# DAC_filter_stage.net
KiCad netlist of a schematic drawn in Altium Designer
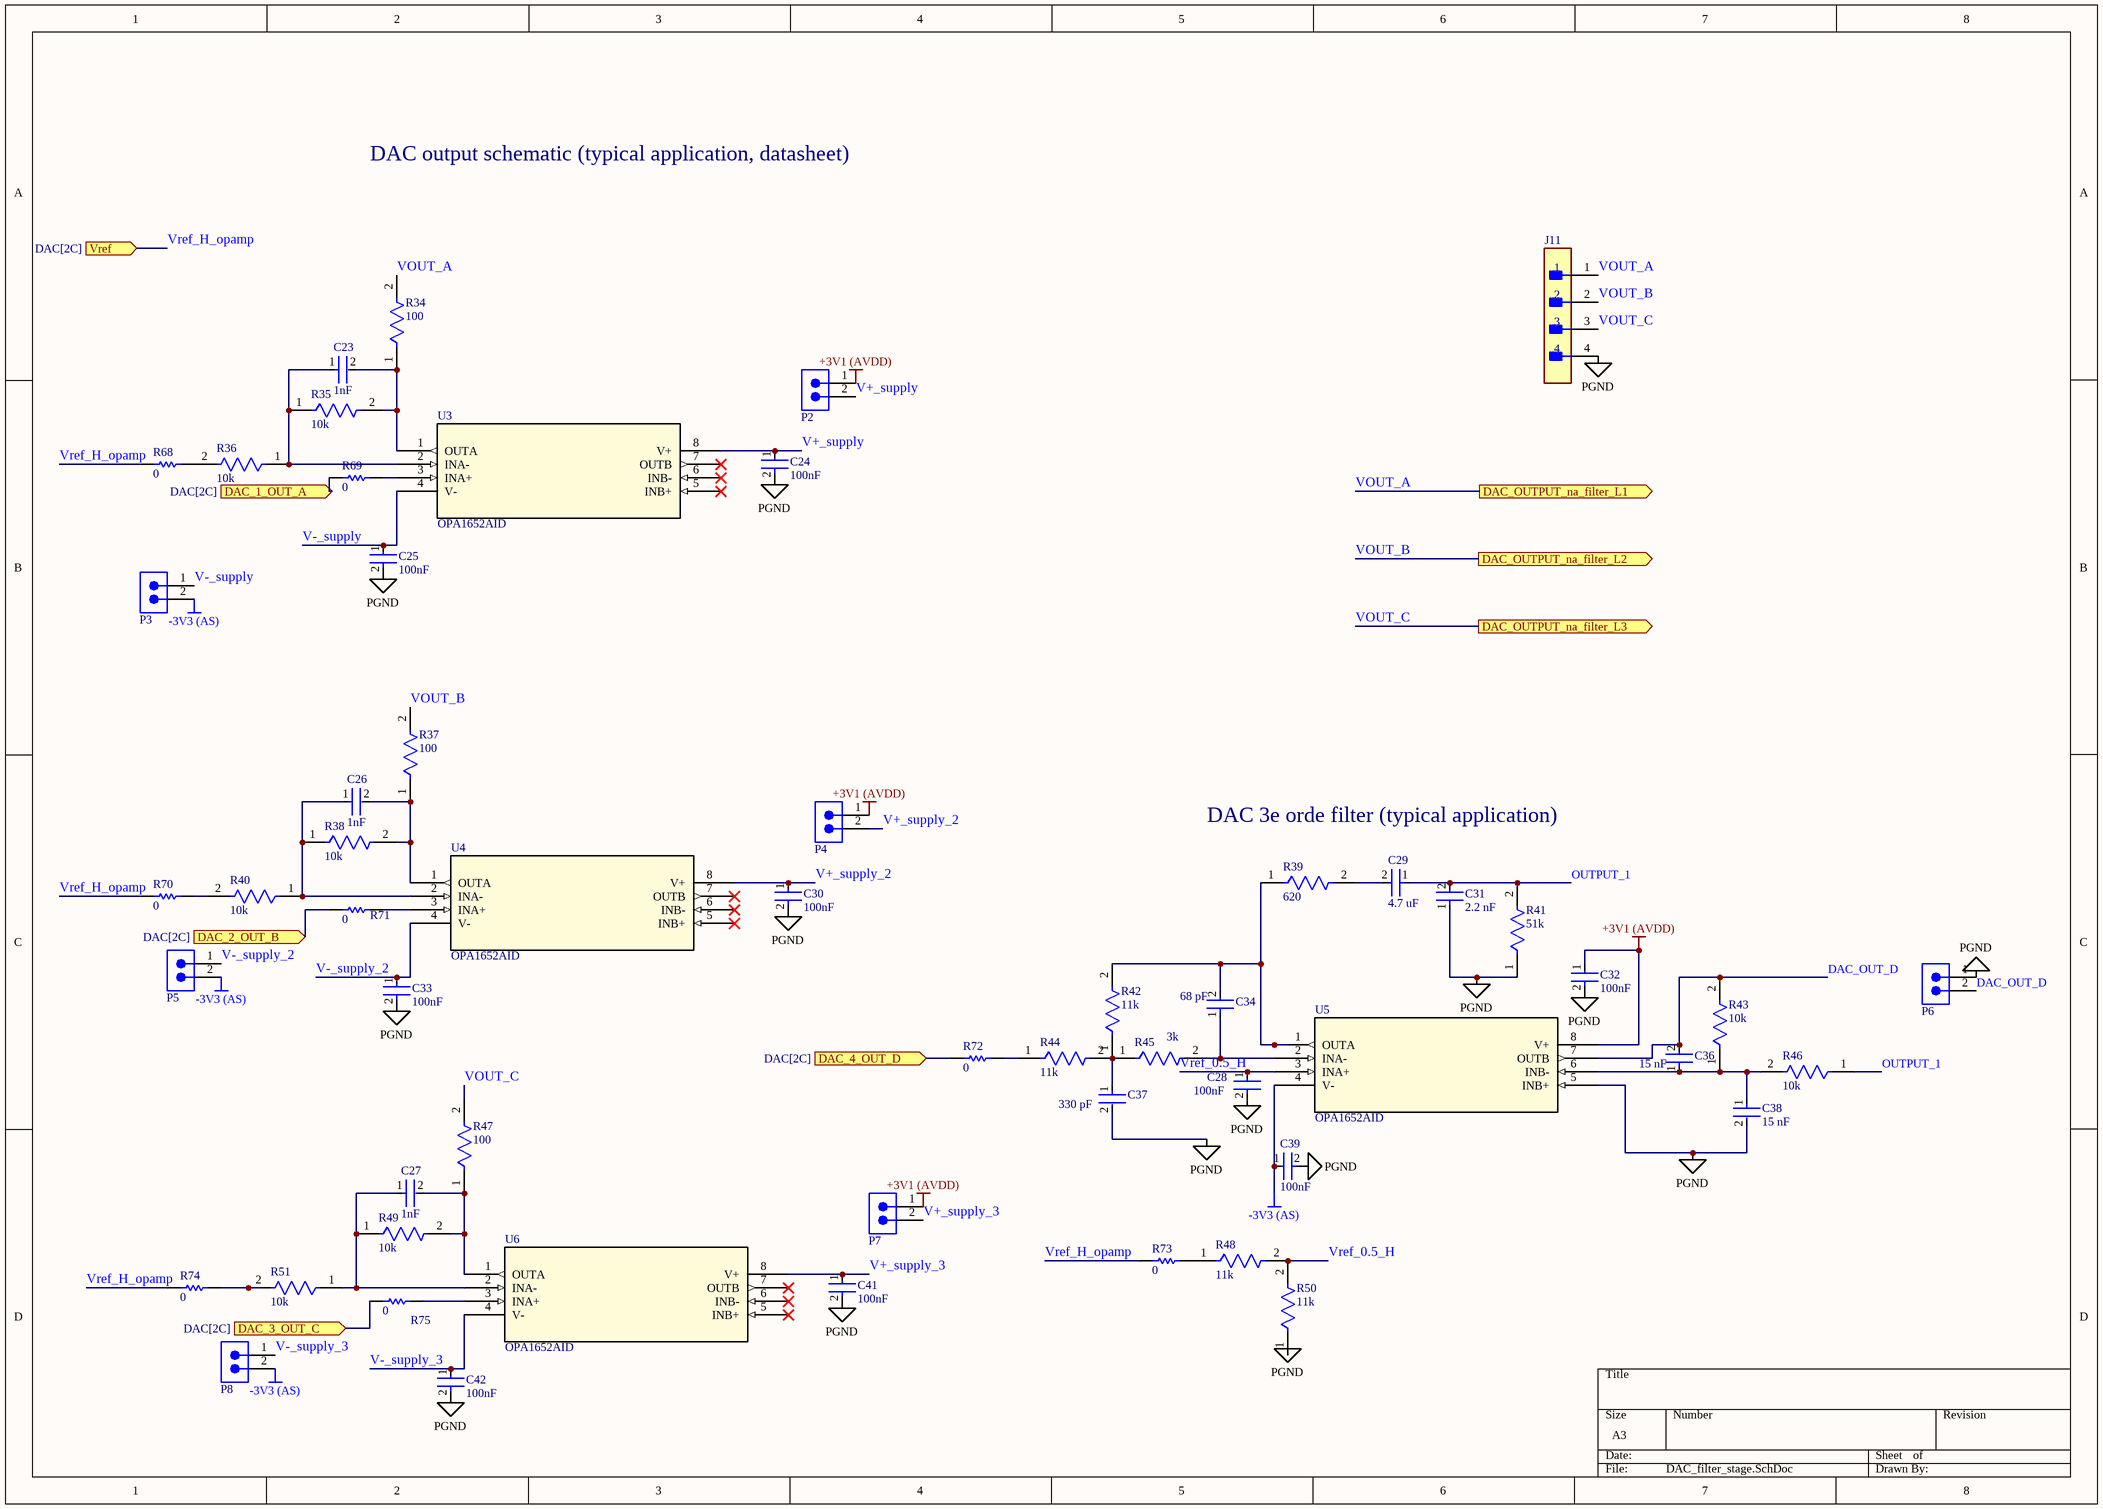
[diagram p0: DAC_filter_stage.SchDoc]

(export (version "E")
  (design (tool "Eeschema 10.0.6"))
  (components
    (comp (ref "C23")
      (value "1nF")
      (footprint "FP-CC0603-DA-MFG")
      (description "General Purpose Ceramic Capacitor, 0603, 1nF, 10%, X7R, 15%, 50V")
      (fields
        (field (name "OCTOPART") "https://octopart.com/cc0603krx7r7bb104-yageo-192941")
        (field (name "TOLERANCE") "0.1")
      )
      (libsource (lib "Altium Content Vault") (part "11868f565c42a9108669ba33697ecf6"))
    )
    (comp (ref "C24")
      (value "100nF")
      (footprint "FP-GRM15-MFG")
      (description "CAP CER 0.1UF 16V X7R 0402")
      (fields (field (name "MANUFACTURER PART NUMBER") "GRM155R71C104KA88D") (field (name "TOLERANCE") "10%"))
      (libsource (lib "Altium Content Vault") (part "236180d848d6139a670b325ea6854c9"))
    )
    (comp (ref "C25")
      (value "100nF")
      (footprint "FP-GRM15-MFG")
      (description "CAP CER 0.1UF 16V X7R 0402")
      (fields (field (name "MANUFACTURER PART NUMBER") "GRM155R71C104KA88D") (field (name "TOLERANCE") "10%"))
      (libsource (lib "Altium Content Vault") (part "236180d848d6139a670b325ea6854c9"))
    )
    (comp (ref "C26")
      (value "1nF")
      (footprint "FP-CC0603-DA-MFG")
      (description "General Purpose Ceramic Capacitor, 0603, 1nF, 10%, X7R, 15%, 50V")
      (fields
        (field (name "OCTOPART") "https://octopart.com/cc0603krx7r7bb104-yageo-192941")
        (field (name "TOLERANCE") "0.1")
      )
      (libsource (lib "Altium Content Vault") (part "11868f565c42a9108669ba33697ecf6"))
    )
    (comp (ref "C27")
      (value "1nF")
      (footprint "FP-CC0603-DA-MFG")
      (description "General Purpose Ceramic Capacitor, 0603, 1nF, 10%, X7R, 15%, 50V")
      (fields
        (field (name "OCTOPART") "https://octopart.com/cc0603krx7r7bb104-yageo-192941")
        (field (name "TOLERANCE") "0.1")
      )
      (libsource (lib "Altium Content Vault") (part "11868f565c42a9108669ba33697ecf6"))
    )
    (comp (ref "C28")
      (value "100nF")
      (footprint "FP-GRM15-MFG")
      (description "CAP CER 0.1UF 16V X7R 0402")
      (fields (field (name "MANUFACTURER PART NUMBER") "GRM155R71C104KA88D") (field (name "TOLERANCE") "10%"))
      (libsource (lib "Altium Content Vault") (part "236180d848d6139a670b325ea6854c9"))
    )
    (comp (ref "C29")
      (value "4.7 uF")
      (footprint "FP-C0603C-CF-MFG")
      (description "CAP CER 4.7 UF 50V 5% X7R 0603")
      (fields (field (name "TOLERANCE") "0.05") (field (name "MANUFACTURER PART NUMBER") "C0603C104J5RACTU"))
      (libsource (lib "Altium Content Vault") (part "b4654b650e69147ec39a6b967a45e02"))
    )
    (comp (ref "C30")
      (value "100nF")
      (footprint "FP-GRM15-MFG")
      (description "CAP CER 0.1UF 16V X7R 0402")
      (fields (field (name "MANUFACTURER PART NUMBER") "GRM155R71C104KA88D") (field (name "TOLERANCE") "10%"))
      (libsource (lib "Altium Content Vault") (part "236180d848d6139a670b325ea6854c9"))
    )
    (comp (ref "C31")
      (value "2.2 nF")
      (footprint "FP-AC0603-MFG")
      (description "AC0603 2.2 pF NP0 5.00% 50 V")
      (fields
        (field (name "TOLERANCE") "0.05")
        (field (name "OCTOPART") "https://octopart.com/ac0603jrnpo9bn271-yageo-87214073")
      )
      (libsource (lib "Altium Content Vault") (part "11868f565c42a9108669ba33697ecf6"))
    )
    (comp (ref "C32")
      (value "100nF")
      (footprint "FP-GRM15-MFG")
      (description "CAP CER 0.1UF 16V X7R 0402")
      (fields (field (name "MANUFACTURER PART NUMBER") "GRM155R71C104KA88D") (field (name "TOLERANCE") "10%"))
      (libsource (lib "Altium Content Vault") (part "236180d848d6139a670b325ea6854c9"))
    )
    (comp (ref "C33")
      (value "100nF")
      (footprint "FP-GRM15-MFG")
      (description "CAP CER 0.1UF 16V X7R 0402")
      (fields (field (name "MANUFACTURER PART NUMBER") "GRM155R71C104KA88D") (field (name "TOLERANCE") "10%"))
      (libsource (lib "Altium Content Vault") (part "236180d848d6139a670b325ea6854c9"))
    )
    (comp (ref "C34")
      (value "68 pF")
      (footprint "FP-AC0603-MFG")
      (description "AC0603 68 pF NP0 5.00% 50 V")
      (fields
        (field (name "TOLERANCE") "0.05")
        (field (name "OCTOPART") "https://octopart.com/ac0603jrnpo9bn271-yageo-87214073")
      )
      (libsource (lib "Altium Content Vault") (part "11868f565c42a9108669ba33697ecf6"))
    )
    (comp (ref "C36")
      (value "15 nF")
      (footprint "FP-C0603C-CF-MFG")
      (fields
        (field (name "TOLERANCE") "0.05")
        (field (name "MANUFACTURER PART NUMBER") "C0603C104J5RACTU")
        (field (name "OCTOPART") "https://octopart.com/c0603c104j5ractu-kemet-10440638")
      )
      (libsource (lib "Altium Content Vault") (part "b4654b650e69147ec39a6b967a45e02"))
    )
    (comp (ref "C37")
      (value "330 pF")
      (footprint "FP-AC0603-MFG")
      (description "AC0603 330 pF NP0 5.00% 50 V")
      (fields
        (field (name "TOLERANCE") "0.05")
        (field (name "OCTOPART") "https://octopart.com/ac0603jrnpo9bn271-yageo-87214073")
      )
      (libsource (lib "Altium Content Vault") (part "11868f565c42a9108669ba33697ecf6"))
    )
    (comp (ref "C38")
      (value "15 nF")
      (footprint "FP-C0603C-CF-MFG")
      (fields
        (field (name "TOLERANCE") "0.05")
        (field (name "MANUFACTURER PART NUMBER") "C0603C104J5RACTU")
        (field (name "OCTOPART") "https://octopart.com/c0603c104j5ractu-kemet-10440638")
      )
      (libsource (lib "Altium Content Vault") (part "b4654b650e69147ec39a6b967a45e02"))
    )
    (comp (ref "C39")
      (value "100nF")
      (footprint "FP-GRM15-MFG")
      (description "CAP CER 0.1UF 16V X7R 0402")
      (fields (field (name "MANUFACTURER PART NUMBER") "GRM155R71C104KA88D") (field (name "TOLERANCE") "10%"))
      (libsource (lib "Altium Content Vault") (part "236180d848d6139a670b325ea6854c9"))
    )
    (comp (ref "C41")
      (value "100nF")
      (footprint "FP-GRM15-MFG")
      (description "CAP CER 0.1UF 16V X7R 0402")
      (fields (field (name "MANUFACTURER PART NUMBER") "GRM155R71C104KA88D") (field (name "TOLERANCE") "10%"))
      (libsource (lib "Altium Content Vault") (part "236180d848d6139a670b325ea6854c9"))
    )
    (comp (ref "C42")
      (value "100nF")
      (footprint "FP-GRM15-MFG")
      (description "CAP CER 0.1UF 16V X7R 0402")
      (fields (field (name "MANUFACTURER PART NUMBER") "GRM155R71C104KA88D") (field (name "TOLERANCE") "10%"))
      (libsource (lib "Altium Content Vault") (part "236180d848d6139a670b325ea6854c9"))
    )
    (comp (ref "J11")
      (value "TSW-104-22-G-S")
      (footprint "FP-TSW-104-22-G-S-MFG")
      (description "GENERIC PART NUMBER: GPHA-1X04\r\nCONN HEADER VERT 4POS 2.54MM")
      (fields (field (name "GENERIC PART NUMBER") "GPHA-1X04"))
      (libsource (lib "Altium Content Vault") (part "299a8cea1bdcbc3624fe62c390fa72c"))
    )
    (comp (ref "P2")
      (value "TSW-102-26-T-S")
      (footprint "SMTC-TSW-102-26-XX-S")
      (description "0.025\" SQ Post Header, Through-hole, Vertical, -55 to 105 degC, 2.54 mm Pitch, 2-Pin, Male, RoHS")
      (fields (field (name "MANUFACTURER") "Samtec"))
      (libsource (lib "Altium Content Vault") (part "SMTC-TSW-102-X-X-S-X"))
    )
    (comp (ref "P3")
      (value "TSW-102-26-T-S")
      (footprint "SMTC-TSW-102-26-XX-S")
      (description "0.025\" SQ Post Header, Through-hole, Vertical, -55 to 105 degC, 2.54 mm Pitch, 2-Pin, Male, RoHS")
      (fields (field (name "MANUFACTURER") "Samtec"))
      (libsource (lib "Altium Content Vault") (part "SMTC-TSW-102-X-X-S-X"))
    )
    (comp (ref "P4")
      (value "TSW-102-26-T-S")
      (footprint "SMTC-TSW-102-26-XX-S")
      (description "0.025\" SQ Post Header, Through-hole, Vertical, -55 to 105 degC, 2.54 mm Pitch, 2-Pin, Male, RoHS")
      (fields (field (name "MANUFACTURER") "Samtec"))
      (libsource (lib "Altium Content Vault") (part "SMTC-TSW-102-X-X-S-X"))
    )
    (comp (ref "P5")
      (value "TSW-102-26-T-S")
      (footprint "SMTC-TSW-102-26-XX-S")
      (description "0.025\" SQ Post Header, Through-hole, Vertical, -55 to 105 degC, 2.54 mm Pitch, 2-Pin, Male, RoHS")
      (fields (field (name "MANUFACTURER") "Samtec"))
      (libsource (lib "Altium Content Vault") (part "SMTC-TSW-102-X-X-S-X"))
    )
    (comp (ref "P6")
      (value "TSW-102-26-T-S")
      (footprint "SMTC-TSW-102-26-XX-S")
      (description "0.025\" SQ Post Header, Through-hole, Vertical, -55 to 105 degC, 2.54 mm Pitch, 2-Pin, Male, RoHS")
      (fields (field (name "MANUFACTURER") "Samtec"))
      (libsource (lib "Altium Content Vault") (part "SMTC-TSW-102-X-X-S-X"))
    )
    (comp (ref "P7")
      (value "TSW-102-26-T-S")
      (footprint "SMTC-TSW-102-26-XX-S")
      (description "0.025\" SQ Post Header, Through-hole, Vertical, -55 to 105 degC, 2.54 mm Pitch, 2-Pin, Male, RoHS")
      (fields (field (name "MANUFACTURER") "Samtec"))
      (libsource (lib "Altium Content Vault") (part "SMTC-TSW-102-X-X-S-X"))
    )
    (comp (ref "P8")
      (value "TSW-102-26-T-S")
      (footprint "SMTC-TSW-102-26-XX-S")
      (description "0.025\" SQ Post Header, Through-hole, Vertical, -55 to 105 degC, 2.54 mm Pitch, 2-Pin, Male, RoHS")
      (fields (field (name "MANUFACTURER") "Samtec"))
      (libsource (lib "Altium Content Vault") (part "SMTC-TSW-102-X-X-S-X"))
    )
    (comp (ref "R34")
      (value "100")
      (footprint "FP-RC1608-IPC_B")
      (description "Res Thick Film 0603 100Ω 1% 0.1W ±100ppm/°C Molded SMD T/R")
      (fields (field (name "TOLERANCE") "1%"))
      (libsource (lib "Altium Content Vault") (part "1029c3af85768c4190bb7ad29bc67b5"))
    )
    (comp (ref "R35")
      (value "10k")
      (footprint "FP-RC1608-IPC_B")
      (description "Res Thick Film 0603 11kΩ 1% 0.1W ±100ppm/°C Molded SMD T/R")
      (fields (field (name "TOLERANCE") "1%"))
      (libsource (lib "Altium Content Vault") (part "1029c3af85768c4190bb7ad29bc67b5"))
    )
    (comp (ref "R36")
      (value "10k")
      (footprint "FP-RC1608-IPC_B")
      (description "Res Thick Film 0603 11kΩ 1% 0.1W ±100ppm/°C Molded SMD T/R")
      (fields (field (name "TOLERANCE") "1%"))
      (libsource (lib "Altium Content Vault") (part "1029c3af85768c4190bb7ad29bc67b5"))
    )
    (comp (ref "R37")
      (value "100")
      (footprint "FP-RC1608-IPC_B")
      (description "Res Thick Film 0603 100Ω 1% 0.1W ±100ppm/°C Molded SMD T/R")
      (fields (field (name "TOLERANCE") "1%"))
      (libsource (lib "Altium Content Vault") (part "1029c3af85768c4190bb7ad29bc67b5"))
    )
    (comp (ref "R38")
      (value "10k")
      (footprint "FP-RC1608-IPC_B")
      (description "Res Thick Film 0603 11kΩ 1% 0.1W ±100ppm/°C Molded SMD T/R")
      (fields (field (name "TOLERANCE") "1%"))
      (libsource (lib "Altium Content Vault") (part "1029c3af85768c4190bb7ad29bc67b5"))
    )
    (comp (ref "R39")
      (value "620")
      (footprint "FP-RC1608-IPC_B")
      (description "Res Thick Film 0603 620Ω 1% 0.1W ±100ppm/°C Molded SMD T/R")
      (fields (field (name "TOLERANCE") "1%"))
      (libsource (lib "Altium Content Vault") (part "1029c3af85768c4190bb7ad29bc67b5"))
    )
    (comp (ref "R40")
      (value "10k")
      (footprint "FP-RC1608-IPC_B")
      (description "Res Thick Film 0603 11kΩ 1% 0.1W ±100ppm/°C Molded SMD T/R")
      (fields (field (name "TOLERANCE") "1%"))
      (libsource (lib "Altium Content Vault") (part "1029c3af85768c4190bb7ad29bc67b5"))
    )
    (comp (ref "R41")
      (value "51k")
      (footprint "FP-RC1608-IPC_B")
      (description "Res Thick Film 0603 51kΩ 1% 0.1W ±100ppm/°C Molded SMD T/R")
      (fields (field (name "TOLERANCE") "1%"))
      (libsource (lib "Altium Content Vault") (part "1029c3af85768c4190bb7ad29bc67b5"))
    )
    (comp (ref "R42")
      (value "11k")
      (footprint "FP-RC1608-IPC_B")
      (description "Res Thick Film 0603 11kΩ 1% 0.1W ±100ppm/°C Molded SMD T/R")
      (fields (field (name "TOLERANCE") "1%"))
      (libsource (lib "Altium Content Vault") (part "1029c3af85768c4190bb7ad29bc67b5"))
    )
    (comp (ref "R43")
      (value "10k")
      (footprint "FP-RC1608-IPC_B")
      (fields (field (name "TOLERANCE") "1%"))
      (libsource (lib "Altium Content Vault") (part "1029c3af85768c4190bb7ad29bc67b5"))
    )
    (comp (ref "R44")
      (value "11k")
      (footprint "FP-RC1608-IPC_B")
      (description "Res Thick Film 0603 11kΩ 1% 0.1W ±100ppm/°C Molded SMD T/R")
      (fields (field (name "TOLERANCE") "1%"))
      (libsource (lib "Altium Content Vault") (part "1029c3af85768c4190bb7ad29bc67b5"))
    )
    (comp (ref "R45")
      (value "3k")
      (footprint "FP-RC1608-IPC_B")
      (description "Res Thick Film 0603 3kΩ 1% 0.1W ±100ppm/°C Molded SMD T/R")
      (fields (field (name "TOLERANCE") "1%"))
      (libsource (lib "Altium Content Vault") (part "1029c3af85768c4190bb7ad29bc67b5"))
    )
    (comp (ref "R46")
      (value "10k")
      (footprint "FP-RC1608-IPC_B")
      (fields (field (name "TOLERANCE") "1%"))
      (libsource (lib "Altium Content Vault") (part "1029c3af85768c4190bb7ad29bc67b5"))
    )
    (comp (ref "R47")
      (value "100")
      (footprint "FP-RC1608-IPC_B")
      (description "Res Thick Film 0603 100Ω 1% 0.1W ±100ppm/°C Molded SMD T/R")
      (fields (field (name "TOLERANCE") "1%"))
      (libsource (lib "Altium Content Vault") (part "1029c3af85768c4190bb7ad29bc67b5"))
    )
    (comp (ref "R48")
      (value "11k")
      (footprint "FP-RC1608-IPC_B")
      (description "Res Thick Film 0603 11kΩ 1% 0.1W ±100ppm/°C Molded SMD T/R")
      (fields (field (name "TOLERANCE") "1%"))
      (libsource (lib "Altium Content Vault") (part "1029c3af85768c4190bb7ad29bc67b5"))
    )
    (comp (ref "R49")
      (value "10k")
      (footprint "FP-RC1608-IPC_B")
      (description "Res Thick Film 0603 11kΩ 1% 0.1W ±100ppm/°C Molded SMD T/R")
      (fields (field (name "TOLERANCE") "1%"))
      (libsource (lib "Altium Content Vault") (part "1029c3af85768c4190bb7ad29bc67b5"))
    )
    (comp (ref "R50")
      (value "11k")
      (footprint "FP-RC1608-IPC_B")
      (description "Res Thick Film 0603 11kΩ 1% 0.1W ±100ppm/°C Molded SMD T/R")
      (fields (field (name "TOLERANCE") "1%"))
      (libsource (lib "Altium Content Vault") (part "1029c3af85768c4190bb7ad29bc67b5"))
    )
    (comp (ref "R51")
      (value "10k")
      (footprint "FP-RC1608-IPC_B")
      (description "Res Thick Film 0603 11kΩ 1% 0.1W ±100ppm/°C Molded SMD T/R")
      (fields (field (name "TOLERANCE") "1%"))
      (libsource (lib "Altium Content Vault") (part "1029c3af85768c4190bb7ad29bc67b5"))
    )
    (comp (ref "R68")
      (value "0")
      (footprint "RESC2013X70X40NL20T20")
      (description "Chip Resistor, 0 Ohm, +/- 1%, 0.125 W, -55 to 155 degC, 0805 (2012 Metric), RoHS, Tape and Reel")
      (fields (field (name "PARTNUMBER") "ERJ-6GEY0R00V") (field (name "TOLERANCE") "5%"))
      (libsource (lib "Altium Content Vault") (part "RES-2"))
    )
    (comp (ref "R69")
      (value "0")
      (footprint "RESC2013X70X40NL20T20")
      (description "Chip Resistor, 0 Ohm, +/- 1%, 0.125 W, -55 to 155 degC, 0805 (2012 Metric), RoHS, Tape and Reel")
      (fields (field (name "PARTNUMBER") "ERJ-6GEY0R00V") (field (name "TOLERANCE") "5%"))
      (libsource (lib "Altium Content Vault") (part "RES-2"))
    )
    (comp (ref "R70")
      (value "0")
      (footprint "RESC2013X70X40NL20T20")
      (description "Chip Resistor, 0 Ohm, +/- 1%, 0.125 W, -55 to 155 degC, 0805 (2012 Metric), RoHS, Tape and Reel")
      (fields (field (name "PARTNUMBER") "ERJ-6GEY0R00V") (field (name "TOLERANCE") "5%"))
      (libsource (lib "Altium Content Vault") (part "RES-2"))
    )
    (comp (ref "R71")
      (value "0")
      (footprint "RESC2013X70X40NL20T20")
      (description "Chip Resistor, 0 Ohm, +/- 1%, 0.125 W, -55 to 155 degC, 0805 (2012 Metric), RoHS, Tape and Reel")
      (fields (field (name "PARTNUMBER") "ERJ-6GEY0R00V") (field (name "TOLERANCE") "5%"))
      (libsource (lib "Altium Content Vault") (part "RES-2"))
    )
    (comp (ref "R72")
      (value "0")
      (footprint "RESC2013X70X40NL20T20")
      (description "Chip Resistor, 0 Ohm, +/- 1%, 0.125 W, -55 to 155 degC, 0805 (2012 Metric), RoHS, Tape and Reel")
      (fields (field (name "PARTNUMBER") "ERJ-6GEY0R00V") (field (name "TOLERANCE") "5%"))
      (libsource (lib "Altium Content Vault") (part "RES-2"))
    )
    (comp (ref "R73")
      (value "0")
      (footprint "RESC2013X70X40NL20T20")
      (description "Chip Resistor, 0 Ohm, +/- 1%, 0.125 W, -55 to 155 degC, 0805 (2012 Metric), RoHS, Tape and Reel")
      (fields (field (name "PARTNUMBER") "ERJ-6GEY0R00V") (field (name "TOLERANCE") "5%"))
      (libsource (lib "Altium Content Vault") (part "RES-2"))
    )
    (comp (ref "R74")
      (value "0")
      (footprint "RESC2013X70X40NL20T20")
      (description "Chip Resistor, 0 Ohm, +/- 1%, 0.125 W, -55 to 155 degC, 0805 (2012 Metric), RoHS, Tape and Reel")
      (fields (field (name "PARTNUMBER") "ERJ-6GEY0R00V") (field (name "TOLERANCE") "5%"))
      (libsource (lib "Altium Content Vault") (part "RES-2"))
    )
    (comp (ref "R75")
      (value "0")
      (footprint "RESC2013X70X40NL20T20")
      (description "Chip Resistor, 0 Ohm, +/- 1%, 0.125 W, -55 to 155 degC, 0805 (2012 Metric), RoHS, Tape and Reel")
      (fields (field (name "PARTNUMBER") "ERJ-6GEY0R00V") (field (name "TOLERANCE") "5%"))
      (libsource (lib "Altium Content Vault") (part "RES-2"))
    )
    (comp (ref "U3")
      (value "OPA1652AID")
      (footprint "D8")
      (description "No Description Available")
      (libsource (lib "OPA1652AID") (part "OPA1652AID"))
    )
    (comp (ref "U4")
      (value "OPA1652AID")
      (footprint "D8")
      (description "No Description Available")
      (libsource (lib "OPA1652AID") (part "OPA1652AID"))
    )
    (comp (ref "U5")
      (value "OPA1652AID")
      (footprint "D8")
      (description "No Description Available")
      (libsource (lib "OPA1652AID") (part "OPA1652AID"))
    )
    (comp (ref "U6")
      (value "OPA1652AID")
      (footprint "D8")
      (description "No Description Available")
      (libsource (lib "OPA1652AID") (part "OPA1652AID"))
    )
  )
  (nets
    (net (code "1") (name "+3V1 (AVDD)") (class "Default")
      (node (ref "C32") (pin "1") (pinfunction "1_1") (pintype "passive"))
      (node (ref "P2") (pin "1") (pinfunction "1_1") (pintype "passive"))
      (node (ref "P4") (pin "1") (pinfunction "1_1") (pintype "passive"))
      (node (ref "P7") (pin "1") (pinfunction "1_1") (pintype "passive"))
      (node (ref "U5") (pin "8") (pinfunction "V+_8") (pintype "power_in"))
    )
    (net (code "2") (name "-3V3 (AS)") (class "Default")
      (node (ref "C39") (pin "1") (pinfunction "1_1") (pintype "passive"))
      (node (ref "P3") (pin "2") (pinfunction "2_2") (pintype "passive"))
      (node (ref "P5") (pin "2") (pinfunction "2_2") (pintype "passive"))
      (node (ref "P8") (pin "2") (pinfunction "2_2") (pintype "passive"))
      (node (ref "U5") (pin "4") (pinfunction "V-_4") (pintype "power_in"))
    )
    (net (code "3") (name "/DAC_1_OUT_A") (class "Default")
      (node (ref "R69") (pin "1") (pinfunction "1_1") (pintype "passive"))
    )
    (net (code "4") (name "/DAC_2_OUT_B") (class "Default")
      (node (ref "R71") (pin "1") (pinfunction "1_1") (pintype "passive"))
    )
    (net (code "5") (name "/DAC_3_OUT_C") (class "Default")
      (node (ref "R75") (pin "1") (pinfunction "1_1") (pintype "passive"))
    )
    (net (code "6") (name "/DAC_4_OUT_D") (class "Default")
      (node (ref "R72") (pin "1") (pinfunction "1_1") (pintype "passive"))
    )
    (net (code "7") (name "/DAC_OUT_D") (class "Default")
      (node (ref "C36") (pin "2") (pinfunction "2_2") (pintype "passive"))
      (node (ref "P6") (pin "2") (pinfunction "2_2") (pintype "passive"))
      (node (ref "R43") (pin "2") (pinfunction "2_2") (pintype "passive"))
      (node (ref "U5") (pin "7") (pinfunction "OUTB_7") (pintype "output"))
    )
    (net (code "8") (name "/OUTPUT_1") (class "Default")
      (node (ref "C29") (pin "1") (pinfunction "1_1") (pintype "passive"))
      (node (ref "C31") (pin "2") (pinfunction "2_2") (pintype "passive"))
      (node (ref "R41") (pin "2") (pinfunction "2_2") (pintype "passive"))
      (node (ref "R46") (pin "1") (pinfunction "1_1") (pintype "passive"))
    )
    (net (code "9") (name "/V+_supply") (class "Default")
      (node (ref "C24") (pin "1") (pinfunction "1_1") (pintype "passive"))
      (node (ref "P2") (pin "2") (pinfunction "2_2") (pintype "passive"))
      (node (ref "U3") (pin "8") (pinfunction "V+_8") (pintype "power_in"))
    )
    (net (code "10") (name "/V+_supply_2") (class "Default")
      (node (ref "C30") (pin "1") (pinfunction "1_1") (pintype "passive"))
      (node (ref "P4") (pin "2") (pinfunction "2_2") (pintype "passive"))
      (node (ref "U4") (pin "8") (pinfunction "V+_8") (pintype "power_in"))
    )
    (net (code "11") (name "/V+_supply_3") (class "Default")
      (node (ref "C41") (pin "1") (pinfunction "1_1") (pintype "passive"))
      (node (ref "P7") (pin "2") (pinfunction "2_2") (pintype "passive"))
      (node (ref "U6") (pin "8") (pinfunction "V+_8") (pintype "power_in"))
    )
    (net (code "12") (name "/V-_supply") (class "Default")
      (node (ref "C25") (pin "1") (pinfunction "1_1") (pintype "passive"))
      (node (ref "P3") (pin "1") (pinfunction "1_1") (pintype "passive"))
      (node (ref "U3") (pin "4") (pinfunction "V-_4") (pintype "power_in"))
    )
    (net (code "13") (name "/V-_supply_2") (class "Default")
      (node (ref "C33") (pin "1") (pinfunction "1_1") (pintype "passive"))
      (node (ref "P5") (pin "1") (pinfunction "1_1") (pintype "passive"))
      (node (ref "U4") (pin "4") (pinfunction "V-_4") (pintype "power_in"))
    )
    (net (code "14") (name "/V-_supply_3") (class "Default")
      (node (ref "C42") (pin "1") (pinfunction "1_1") (pintype "passive"))
      (node (ref "P8") (pin "1") (pinfunction "1_1") (pintype "passive"))
      (node (ref "U6") (pin "4") (pinfunction "V-_4") (pintype "power_in"))
    )
    (net (code "15") (name "/VOUT_A") (class "Default")
      (node (ref "J11") (pin "1") (pinfunction "1_1") (pintype "passive"))
      (node (ref "R34") (pin "2") (pinfunction "2_2") (pintype "passive"))
    )
    (net (code "16") (name "/VOUT_B") (class "Default")
      (node (ref "J11") (pin "2") (pinfunction "2_2") (pintype "passive"))
      (node (ref "R37") (pin "2") (pinfunction "2_2") (pintype "passive"))
    )
    (net (code "17") (name "/VOUT_C") (class "Default")
      (node (ref "J11") (pin "3") (pinfunction "3_3") (pintype "passive"))
      (node (ref "R47") (pin "2") (pinfunction "2_2") (pintype "passive"))
    )
    (net (code "18") (name "/Vref_0.5_H") (class "Default")
      (node (ref "C28") (pin "1") (pinfunction "1_1") (pintype "passive"))
      (node (ref "R48") (pin "2") (pinfunction "2_2") (pintype "passive"))
      (node (ref "R50") (pin "2") (pinfunction "2_2") (pintype "passive"))
      (node (ref "U5") (pin "3") (pinfunction "INA+_3") (pintype "input"))
    )
    (net (code "19") (name "/Vref_H_opamp") (class "Default")
      (node (ref "R68") (pin "1") (pinfunction "1_1") (pintype "passive"))
      (node (ref "R70") (pin "1") (pinfunction "1_1") (pintype "passive"))
      (node (ref "R73") (pin "1") (pinfunction "1_1") (pintype "passive"))
      (node (ref "R74") (pin "1") (pinfunction "1_1") (pintype "passive"))
    )
    (net (code "20") (name "Net-(C29-Pad2)") (class "Default")
      (node (ref "C29") (pin "2") (pinfunction "2_2") (pintype "passive"))
      (node (ref "R39") (pin "2") (pinfunction "2_2") (pintype "passive"))
    )
    (net (code "21") (name "Net-(C37-Pad1)") (class "Default")
      (node (ref "C37") (pin "1") (pinfunction "1_1") (pintype "passive"))
      (node (ref "R42") (pin "1") (pinfunction "1_1") (pintype "passive"))
      (node (ref "R44") (pin "2") (pinfunction "2_2") (pintype "passive"))
      (node (ref "R45") (pin "1") (pinfunction "1_1") (pintype "passive"))
    )
    (net (code "22") (name "Net-(R36-Pad2)") (class "Default")
      (node (ref "R36") (pin "2") (pinfunction "2_2") (pintype "passive"))
      (node (ref "R68") (pin "2") (pinfunction "2_2") (pintype "passive"))
    )
    (net (code "23") (name "Net-(R40-Pad2)") (class "Default")
      (node (ref "R40") (pin "2") (pinfunction "2_2") (pintype "passive"))
      (node (ref "R70") (pin "2") (pinfunction "2_2") (pintype "passive"))
    )
    (net (code "24") (name "Net-(R44-Pad1)") (class "Default")
      (node (ref "R44") (pin "1") (pinfunction "1_1") (pintype "passive"))
      (node (ref "R72") (pin "2") (pinfunction "2_2") (pintype "passive"))
    )
    (net (code "25") (name "Net-(R48-Pad1)") (class "Default")
      (node (ref "R48") (pin "1") (pinfunction "1_1") (pintype "passive"))
      (node (ref "R73") (pin "2") (pinfunction "2_2") (pintype "passive"))
    )
    (net (code "26") (name "Net-(R51-Pad2)") (class "Default")
      (node (ref "R51") (pin "2") (pinfunction "2_2") (pintype "passive"))
      (node (ref "R74") (pin "2") (pinfunction "2_2") (pintype "passive"))
    )
    (net (code "27") (name "Net-(U3-INA+)") (class "Default")
      (node (ref "R69") (pin "2") (pinfunction "2_2") (pintype "passive"))
      (node (ref "U3") (pin "3") (pinfunction "INA+_3") (pintype "input"))
    )
    (net (code "28") (name "Net-(U3-INA-)") (class "Default")
      (node (ref "C23") (pin "1") (pinfunction "1_1") (pintype "passive"))
      (node (ref "R35") (pin "1") (pinfunction "1_1") (pintype "passive"))
      (node (ref "R36") (pin "1") (pinfunction "1_1") (pintype "passive"))
      (node (ref "U3") (pin "2") (pinfunction "INA-_2") (pintype "input"))
    )
    (net (code "29") (name "Net-(U3-OUTA)") (class "Default")
      (node (ref "C23") (pin "2") (pinfunction "2_2") (pintype "passive"))
      (node (ref "R34") (pin "1") (pinfunction "1_1") (pintype "passive"))
      (node (ref "R35") (pin "2") (pinfunction "2_2") (pintype "passive"))
      (node (ref "U3") (pin "1") (pinfunction "OUTA_1") (pintype "output"))
    )
    (net (code "30") (name "Net-(U4-INA+)") (class "Default")
      (node (ref "R71") (pin "2") (pinfunction "2_2") (pintype "passive"))
      (node (ref "U4") (pin "3") (pinfunction "INA+_3") (pintype "input"))
    )
    (net (code "31") (name "Net-(U4-INA-)") (class "Default")
      (node (ref "C26") (pin "1") (pinfunction "1_1") (pintype "passive"))
      (node (ref "R38") (pin "1") (pinfunction "1_1") (pintype "passive"))
      (node (ref "R40") (pin "1") (pinfunction "1_1") (pintype "passive"))
      (node (ref "U4") (pin "2") (pinfunction "INA-_2") (pintype "input"))
    )
    (net (code "32") (name "Net-(U4-OUTA)") (class "Default")
      (node (ref "C26") (pin "2") (pinfunction "2_2") (pintype "passive"))
      (node (ref "R37") (pin "1") (pinfunction "1_1") (pintype "passive"))
      (node (ref "R38") (pin "2") (pinfunction "2_2") (pintype "passive"))
      (node (ref "U4") (pin "1") (pinfunction "OUTA_1") (pintype "output"))
    )
    (net (code "33") (name "Net-(U5-INA-)") (class "Default")
      (node (ref "C34") (pin "1") (pinfunction "1_1") (pintype "passive"))
      (node (ref "R45") (pin "2") (pinfunction "2_2") (pintype "passive"))
      (node (ref "U5") (pin "2") (pinfunction "INA-_2") (pintype "input"))
    )
    (net (code "34") (name "Net-(U5-INB-)") (class "Default")
      (node (ref "C36") (pin "1") (pinfunction "1_1") (pintype "passive"))
      (node (ref "C38") (pin "1") (pinfunction "1_1") (pintype "passive"))
      (node (ref "R43") (pin "1") (pinfunction "1_1") (pintype "passive"))
      (node (ref "R46") (pin "2") (pinfunction "2_2") (pintype "passive"))
      (node (ref "U5") (pin "6") (pinfunction "INB-_6") (pintype "input"))
    )
    (net (code "35") (name "Net-(U5-OUTA)") (class "Default")
      (node (ref "C34") (pin "2") (pinfunction "2_2") (pintype "passive"))
      (node (ref "R39") (pin "1") (pinfunction "1_1") (pintype "passive"))
      (node (ref "R42") (pin "2") (pinfunction "2_2") (pintype "passive"))
      (node (ref "U5") (pin "1") (pinfunction "OUTA_1") (pintype "output"))
    )
    (net (code "36") (name "Net-(U6-INA+)") (class "Default")
      (node (ref "R75") (pin "2") (pinfunction "2_2") (pintype "passive"))
      (node (ref "U6") (pin "3") (pinfunction "INA+_3") (pintype "input"))
    )
    (net (code "37") (name "Net-(U6-INA-)") (class "Default")
      (node (ref "C27") (pin "1") (pinfunction "1_1") (pintype "passive"))
      (node (ref "R49") (pin "1") (pinfunction "1_1") (pintype "passive"))
      (node (ref "R51") (pin "1") (pinfunction "1_1") (pintype "passive"))
      (node (ref "U6") (pin "2") (pinfunction "INA-_2") (pintype "input"))
    )
    (net (code "38") (name "Net-(U6-OUTA)") (class "Default")
      (node (ref "C27") (pin "2") (pinfunction "2_2") (pintype "passive"))
      (node (ref "R47") (pin "1") (pinfunction "1_1") (pintype "passive"))
      (node (ref "R49") (pin "2") (pinfunction "2_2") (pintype "passive"))
      (node (ref "U6") (pin "1") (pinfunction "OUTA_1") (pintype "output"))
    )
    (net (code "39") (name "PGND") (class "Default")
      (node (ref "C24") (pin "2") (pinfunction "2_2") (pintype "passive"))
      (node (ref "C25") (pin "2") (pinfunction "2_2") (pintype "passive"))
      (node (ref "C28") (pin "2") (pinfunction "2_2") (pintype "passive"))
      (node (ref "C30") (pin "2") (pinfunction "2_2") (pintype "passive"))
      (node (ref "C31") (pin "1") (pinfunction "1_1") (pintype "passive"))
      (node (ref "C32") (pin "2") (pinfunction "2_2") (pintype "passive"))
      (node (ref "C33") (pin "2") (pinfunction "2_2") (pintype "passive"))
      (node (ref "C37") (pin "2") (pinfunction "2_2") (pintype "passive"))
      (node (ref "C38") (pin "2") (pinfunction "2_2") (pintype "passive"))
      (node (ref "C39") (pin "2") (pinfunction "2_2") (pintype "passive"))
      (node (ref "C41") (pin "2") (pinfunction "2_2") (pintype "passive"))
      (node (ref "C42") (pin "2") (pinfunction "2_2") (pintype "passive"))
      (node (ref "J11") (pin "4") (pinfunction "4_4") (pintype "passive"))
      (node (ref "P6") (pin "1") (pinfunction "1_1") (pintype "passive"))
      (node (ref "R41") (pin "1") (pinfunction "1_1") (pintype "passive"))
      (node (ref "U5") (pin "5") (pinfunction "INB+_5") (pintype "input"))
    )
    (net (code "40") (name "unconnected-(R50-Pad1)") (class "Default")
      (node (ref "R50") (pin "1") (pinfunction "1_1") (pintype "passive"))
    )
    (net (code "41") (name "unconnected-(U3-INB+-Pad5)") (class "Default")
      (node (ref "U3") (pin "5") (pinfunction "INB+_5") (pintype "input+no_connect"))
    )
    (net (code "42") (name "unconnected-(U3-INB--Pad6)") (class "Default")
      (node (ref "U3") (pin "6") (pinfunction "INB-_6") (pintype "input+no_connect"))
    )
    (net (code "43") (name "unconnected-(U3-OUTB-Pad7)") (class "Default")
      (node (ref "U3") (pin "7") (pinfunction "OUTB_7") (pintype "output+no_connect"))
    )
    (net (code "44") (name "unconnected-(U4-INB+-Pad5)") (class "Default")
      (node (ref "U4") (pin "5") (pinfunction "INB+_5") (pintype "input+no_connect"))
    )
    (net (code "45") (name "unconnected-(U4-INB--Pad6)") (class "Default")
      (node (ref "U4") (pin "6") (pinfunction "INB-_6") (pintype "input+no_connect"))
    )
    (net (code "46") (name "unconnected-(U4-OUTB-Pad7)") (class "Default")
      (node (ref "U4") (pin "7") (pinfunction "OUTB_7") (pintype "output+no_connect"))
    )
    (net (code "47") (name "unconnected-(U6-INB+-Pad5)") (class "Default")
      (node (ref "U6") (pin "5") (pinfunction "INB+_5") (pintype "input+no_connect"))
    )
    (net (code "48") (name "unconnected-(U6-INB--Pad6)") (class "Default")
      (node (ref "U6") (pin "6") (pinfunction "INB-_6") (pintype "input+no_connect"))
    )
    (net (code "49") (name "unconnected-(U6-OUTB-Pad7)") (class "Default")
      (node (ref "U6") (pin "7") (pinfunction "OUTB_7") (pintype "output+no_connect"))
    )
  )
)
